# moc2.net
KiCad netlist of a schematic drawn in EAGLE
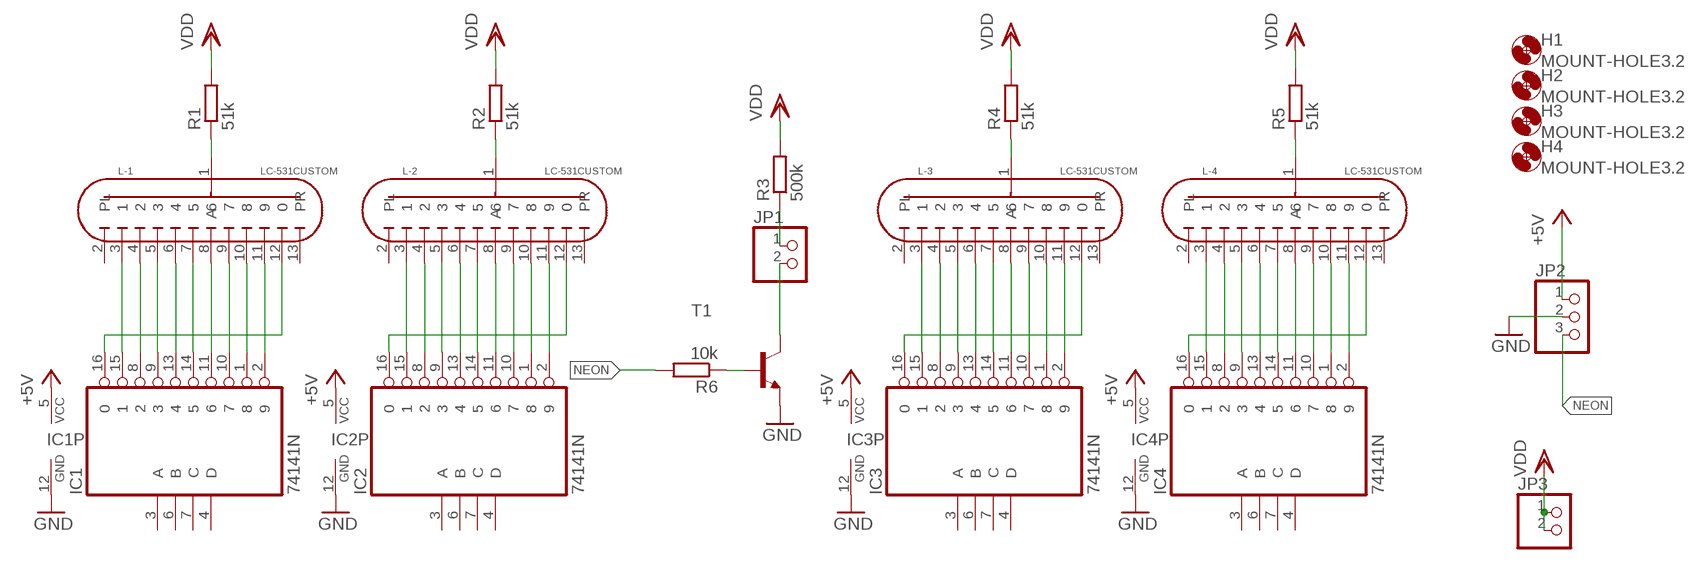
[diagram p0: schematic, sheet 1]

(export (version "E")
  (design (tool "Eeschema 10.0.6"))
  (components
    (comp (ref "H1")
      (value "MOUNT-HOLE3.2")
      (footprint "eagle-import:3,2")
      (libsource (lib "eagle-import") (part "MOUNT-HOLE3.2"))
    )
    (comp (ref "H2")
      (value "MOUNT-HOLE3.2")
      (footprint "eagle-import:3,2")
      (libsource (lib "eagle-import") (part "MOUNT-HOLE3.2"))
    )
    (comp (ref "H3")
      (value "MOUNT-HOLE3.2")
      (footprint "eagle-import:3,2")
      (libsource (lib "eagle-import") (part "MOUNT-HOLE3.2"))
    )
    (comp (ref "H4")
      (value "MOUNT-HOLE3.2")
      (footprint "eagle-import:3,2")
      (libsource (lib "eagle-import") (part "MOUNT-HOLE3.2"))
    )
    (comp (ref "IC1")
      (value "74141N")
      (footprint "eagle-import:DIL16")
      (fields (field (name "SPICEPREFIX") "X"))
      (libsource (lib "eagle-import") (part "74141N"))
    )
    (comp (ref "IC2")
      (value "74141N")
      (footprint "eagle-import:DIL16")
      (libsource (lib "eagle-import") (part "74141N"))
    )
    (comp (ref "IC3")
      (value "74141N")
      (footprint "eagle-import:DIL16")
      (fields (field (name "SPICEPREFIX") "X"))
      (libsource (lib "eagle-import") (part "74141N"))
    )
    (comp (ref "IC4")
      (value "74141N")
      (footprint "eagle-import:DIL16")
      (libsource (lib "eagle-import") (part "74141N"))
    )
    (comp (ref "JP1")
      (value "PINHD-1X2")
      (footprint "eagle-import:1X02")
      (libsource (lib "eagle-import") (part "PINHD-1X2"))
    )
    (comp (ref "JP2")
      (value "PINHD-1X3/90")
      (footprint "eagle-import:1X03_90")
      (libsource (lib "eagle-import") (part "PINHD-1X3/90"))
    )
    (comp (ref "JP3")
      (value "PINHD-1X2/90")
      (footprint "eagle-import:1X02_90")
      (libsource (lib "eagle-import") (part "PINHD-1X2/90"))
    )
    (comp (ref "L-1")
      (value "LC-531CUSTOM")
      (footprint "eagle-import:LC-531_PIN_SOCKET")
      (libsource (lib "eagle-import") (part "LC-531CUSTOM"))
    )
    (comp (ref "L-2")
      (value "LC-531CUSTOM")
      (footprint "eagle-import:LC-531_PIN_SOCKET")
      (libsource (lib "eagle-import") (part "LC-531CUSTOM"))
    )
    (comp (ref "L-3")
      (value "LC-531CUSTOM")
      (footprint "eagle-import:LC-531_PIN_SOCKET")
      (libsource (lib "eagle-import") (part "LC-531CUSTOM"))
    )
    (comp (ref "L-4")
      (value "LC-531CUSTOM")
      (footprint "eagle-import:LC-531_PIN_SOCKET")
      (libsource (lib "eagle-import") (part "LC-531CUSTOM"))
    )
    (comp (ref "R1")
      (value "51k")
      (footprint "eagle-import:0207_10")
      (libsource (lib "eagle-import") (part "R-EU_0207/10"))
    )
    (comp (ref "R2")
      (value "51k")
      (footprint "eagle-import:0207_10")
      (libsource (lib "eagle-import") (part "R-EU_0207/10"))
    )
    (comp (ref "R3")
      (value "500k")
      (footprint "eagle-import:0207_10")
      (libsource (lib "eagle-import") (part "R-EU_0207/10"))
    )
    (comp (ref "R4")
      (value "51k")
      (footprint "eagle-import:0207_10")
      (libsource (lib "eagle-import") (part "R-EU_0207/10"))
    )
    (comp (ref "R5")
      (value "51k")
      (footprint "eagle-import:0207_10")
      (libsource (lib "eagle-import") (part "R-EU_0207/10"))
    )
    (comp (ref "R6")
      (value "10k")
      (footprint "eagle-import:0207_10")
      (libsource (lib "eagle-import") (part "R-EU_0207/10"))
    )
    (comp (ref "T1")
      (value "BF422-NPN-TO92-BCE")
      (footprint "eagle-import:TO92-BCE")
      (libsource (lib "eagle-import") (part "-NPN-TO92-BCEBF422"))
    )
  )
  (nets
    (net (code "1") (name "+5V") (class "Default")
      (node (ref "IC1") (pin "5") (pinfunction "VCC_5") (pintype "power_in"))
      (node (ref "IC2") (pin "5") (pinfunction "VCC_5") (pintype "power_in"))
      (node (ref "IC3") (pin "5") (pinfunction "VCC_5") (pintype "power_in"))
      (node (ref "IC4") (pin "5") (pinfunction "VCC_5") (pintype "power_in"))
      (node (ref "JP2") (pin "1") (pinfunction "1_1") (pintype "passive"))
    )
    (net (code "2") (name "GND") (class "Default")
      (node (ref "IC1") (pin "12") (pinfunction "GND_12") (pintype "power_in"))
      (node (ref "IC2") (pin "12") (pinfunction "GND_12") (pintype "power_in"))
      (node (ref "IC3") (pin "12") (pinfunction "GND_12") (pintype "power_in"))
      (node (ref "IC4") (pin "12") (pinfunction "GND_12") (pintype "power_in"))
      (node (ref "JP2") (pin "2") (pinfunction "2_2") (pintype "passive"))
      (node (ref "T1") (pin "E") (pinfunction "E_E") (pintype "passive"))
    )
    (net (code "3") (name "NEON") (class "Default")
      (node (ref "JP2") (pin "3") (pinfunction "3_3") (pintype "passive"))
      (node (ref "R6") (pin "2") (pinfunction "2_2") (pintype "passive"))
    )
    (net (code "4") (name "Net-(IC1A-0)") (class "Default")
      (node (ref "IC1") (pin "16") (pinfunction "0_16") (pintype "open_collector"))
      (node (ref "L-1") (pin "12") (pinfunction "0_12") (pintype "bidirectional"))
    )
    (net (code "5") (name "Net-(IC1A-1)") (class "Default")
      (node (ref "IC1") (pin "15") (pinfunction "1_15") (pintype "open_collector"))
      (node (ref "L-1") (pin "3") (pinfunction "1_3") (pintype "bidirectional"))
    )
    (net (code "6") (name "Net-(IC1A-2)") (class "Default")
      (node (ref "IC1") (pin "8") (pinfunction "2_8") (pintype "open_collector"))
      (node (ref "L-1") (pin "4") (pinfunction "2_4") (pintype "bidirectional"))
    )
    (net (code "7") (name "Net-(IC1A-3)") (class "Default")
      (node (ref "IC1") (pin "9") (pinfunction "3_9") (pintype "open_collector"))
      (node (ref "L-1") (pin "5") (pinfunction "3_5") (pintype "bidirectional"))
    )
    (net (code "8") (name "Net-(IC1A-4)") (class "Default")
      (node (ref "IC1") (pin "13") (pinfunction "4_13") (pintype "open_collector"))
      (node (ref "L-1") (pin "6") (pinfunction "4_6") (pintype "bidirectional"))
    )
    (net (code "9") (name "Net-(IC1A-5)") (class "Default")
      (node (ref "IC1") (pin "14") (pinfunction "5_14") (pintype "open_collector"))
      (node (ref "L-1") (pin "7") (pinfunction "5_7") (pintype "bidirectional"))
    )
    (net (code "10") (name "Net-(IC1A-6)") (class "Default")
      (node (ref "IC1") (pin "11") (pinfunction "6_11") (pintype "open_collector"))
      (node (ref "L-1") (pin "8") (pinfunction "6_8") (pintype "bidirectional"))
    )
    (net (code "11") (name "Net-(IC1A-7)") (class "Default")
      (node (ref "IC1") (pin "10") (pinfunction "7_10") (pintype "open_collector"))
      (node (ref "L-1") (pin "9") (pinfunction "7_9") (pintype "bidirectional"))
    )
    (net (code "12") (name "Net-(IC1A-8)") (class "Default")
      (node (ref "IC1") (pin "1") (pinfunction "8_1") (pintype "open_collector"))
      (node (ref "L-1") (pin "10") (pinfunction "8_10") (pintype "bidirectional"))
    )
    (net (code "13") (name "Net-(IC1A-9)") (class "Default")
      (node (ref "IC1") (pin "2") (pinfunction "9_2") (pintype "open_collector"))
      (node (ref "L-1") (pin "11") (pinfunction "9_11") (pintype "bidirectional"))
    )
    (net (code "14") (name "Net-(IC2A-0)") (class "Default")
      (node (ref "IC2") (pin "16") (pinfunction "0_16") (pintype "open_collector"))
      (node (ref "L-2") (pin "12") (pinfunction "0_12") (pintype "bidirectional"))
    )
    (net (code "15") (name "Net-(IC2A-1)") (class "Default")
      (node (ref "IC2") (pin "15") (pinfunction "1_15") (pintype "open_collector"))
      (node (ref "L-2") (pin "3") (pinfunction "1_3") (pintype "bidirectional"))
    )
    (net (code "16") (name "Net-(IC2A-2)") (class "Default")
      (node (ref "IC2") (pin "8") (pinfunction "2_8") (pintype "open_collector"))
      (node (ref "L-2") (pin "4") (pinfunction "2_4") (pintype "bidirectional"))
    )
    (net (code "17") (name "Net-(IC2A-3)") (class "Default")
      (node (ref "IC2") (pin "9") (pinfunction "3_9") (pintype "open_collector"))
      (node (ref "L-2") (pin "5") (pinfunction "3_5") (pintype "bidirectional"))
    )
    (net (code "18") (name "Net-(IC2A-4)") (class "Default")
      (node (ref "IC2") (pin "13") (pinfunction "4_13") (pintype "open_collector"))
      (node (ref "L-2") (pin "6") (pinfunction "4_6") (pintype "bidirectional"))
    )
    (net (code "19") (name "Net-(IC2A-5)") (class "Default")
      (node (ref "IC2") (pin "14") (pinfunction "5_14") (pintype "open_collector"))
      (node (ref "L-2") (pin "7") (pinfunction "5_7") (pintype "bidirectional"))
    )
    (net (code "20") (name "Net-(IC2A-6)") (class "Default")
      (node (ref "IC2") (pin "11") (pinfunction "6_11") (pintype "open_collector"))
      (node (ref "L-2") (pin "8") (pinfunction "6_8") (pintype "bidirectional"))
    )
    (net (code "21") (name "Net-(IC2A-7)") (class "Default")
      (node (ref "IC2") (pin "10") (pinfunction "7_10") (pintype "open_collector"))
      (node (ref "L-2") (pin "9") (pinfunction "7_9") (pintype "bidirectional"))
    )
    (net (code "22") (name "Net-(IC2A-8)") (class "Default")
      (node (ref "IC2") (pin "1") (pinfunction "8_1") (pintype "open_collector"))
      (node (ref "L-2") (pin "10") (pinfunction "8_10") (pintype "bidirectional"))
    )
    (net (code "23") (name "Net-(IC2A-9)") (class "Default")
      (node (ref "IC2") (pin "2") (pinfunction "9_2") (pintype "open_collector"))
      (node (ref "L-2") (pin "11") (pinfunction "9_11") (pintype "bidirectional"))
    )
    (net (code "24") (name "Net-(IC3A-0)") (class "Default")
      (node (ref "IC3") (pin "16") (pinfunction "0_16") (pintype "open_collector"))
      (node (ref "L-3") (pin "12") (pinfunction "0_12") (pintype "bidirectional"))
    )
    (net (code "25") (name "Net-(IC3A-1)") (class "Default")
      (node (ref "IC3") (pin "15") (pinfunction "1_15") (pintype "open_collector"))
      (node (ref "L-3") (pin "3") (pinfunction "1_3") (pintype "bidirectional"))
    )
    (net (code "26") (name "Net-(IC3A-2)") (class "Default")
      (node (ref "IC3") (pin "8") (pinfunction "2_8") (pintype "open_collector"))
      (node (ref "L-3") (pin "4") (pinfunction "2_4") (pintype "bidirectional"))
    )
    (net (code "27") (name "Net-(IC3A-3)") (class "Default")
      (node (ref "IC3") (pin "9") (pinfunction "3_9") (pintype "open_collector"))
      (node (ref "L-3") (pin "5") (pinfunction "3_5") (pintype "bidirectional"))
    )
    (net (code "28") (name "Net-(IC3A-4)") (class "Default")
      (node (ref "IC3") (pin "13") (pinfunction "4_13") (pintype "open_collector"))
      (node (ref "L-3") (pin "6") (pinfunction "4_6") (pintype "bidirectional"))
    )
    (net (code "29") (name "Net-(IC3A-5)") (class "Default")
      (node (ref "IC3") (pin "14") (pinfunction "5_14") (pintype "open_collector"))
      (node (ref "L-3") (pin "7") (pinfunction "5_7") (pintype "bidirectional"))
    )
    (net (code "30") (name "Net-(IC3A-6)") (class "Default")
      (node (ref "IC3") (pin "11") (pinfunction "6_11") (pintype "open_collector"))
      (node (ref "L-3") (pin "8") (pinfunction "6_8") (pintype "bidirectional"))
    )
    (net (code "31") (name "Net-(IC3A-7)") (class "Default")
      (node (ref "IC3") (pin "10") (pinfunction "7_10") (pintype "open_collector"))
      (node (ref "L-3") (pin "9") (pinfunction "7_9") (pintype "bidirectional"))
    )
    (net (code "32") (name "Net-(IC3A-8)") (class "Default")
      (node (ref "IC3") (pin "1") (pinfunction "8_1") (pintype "open_collector"))
      (node (ref "L-3") (pin "10") (pinfunction "8_10") (pintype "bidirectional"))
    )
    (net (code "33") (name "Net-(IC3A-9)") (class "Default")
      (node (ref "IC3") (pin "2") (pinfunction "9_2") (pintype "open_collector"))
      (node (ref "L-3") (pin "11") (pinfunction "9_11") (pintype "bidirectional"))
    )
    (net (code "34") (name "Net-(IC4A-0)") (class "Default")
      (node (ref "IC4") (pin "16") (pinfunction "0_16") (pintype "open_collector"))
      (node (ref "L-4") (pin "12") (pinfunction "0_12") (pintype "bidirectional"))
    )
    (net (code "35") (name "Net-(IC4A-1)") (class "Default")
      (node (ref "IC4") (pin "15") (pinfunction "1_15") (pintype "open_collector"))
      (node (ref "L-4") (pin "3") (pinfunction "1_3") (pintype "bidirectional"))
    )
    (net (code "36") (name "Net-(IC4A-2)") (class "Default")
      (node (ref "IC4") (pin "8") (pinfunction "2_8") (pintype "open_collector"))
      (node (ref "L-4") (pin "4") (pinfunction "2_4") (pintype "bidirectional"))
    )
    (net (code "37") (name "Net-(IC4A-3)") (class "Default")
      (node (ref "IC4") (pin "9") (pinfunction "3_9") (pintype "open_collector"))
      (node (ref "L-4") (pin "5") (pinfunction "3_5") (pintype "bidirectional"))
    )
    (net (code "38") (name "Net-(IC4A-4)") (class "Default")
      (node (ref "IC4") (pin "13") (pinfunction "4_13") (pintype "open_collector"))
      (node (ref "L-4") (pin "6") (pinfunction "4_6") (pintype "bidirectional"))
    )
    (net (code "39") (name "Net-(IC4A-5)") (class "Default")
      (node (ref "IC4") (pin "14") (pinfunction "5_14") (pintype "open_collector"))
      (node (ref "L-4") (pin "7") (pinfunction "5_7") (pintype "bidirectional"))
    )
    (net (code "40") (name "Net-(IC4A-6)") (class "Default")
      (node (ref "IC4") (pin "11") (pinfunction "6_11") (pintype "open_collector"))
      (node (ref "L-4") (pin "8") (pinfunction "6_8") (pintype "bidirectional"))
    )
    (net (code "41") (name "Net-(IC4A-7)") (class "Default")
      (node (ref "IC4") (pin "10") (pinfunction "7_10") (pintype "open_collector"))
      (node (ref "L-4") (pin "9") (pinfunction "7_9") (pintype "bidirectional"))
    )
    (net (code "42") (name "Net-(IC4A-8)") (class "Default")
      (node (ref "IC4") (pin "1") (pinfunction "8_1") (pintype "open_collector"))
      (node (ref "L-4") (pin "10") (pinfunction "8_10") (pintype "bidirectional"))
    )
    (net (code "43") (name "Net-(IC4A-9)") (class "Default")
      (node (ref "IC4") (pin "2") (pinfunction "9_2") (pintype "open_collector"))
      (node (ref "L-4") (pin "11") (pinfunction "9_11") (pintype "bidirectional"))
    )
    (net (code "44") (name "Net-(JP1-Pad1)") (class "Default")
      (node (ref "JP1") (pin "1") (pinfunction "1_1") (pintype "passive"))
      (node (ref "R3") (pin "1") (pinfunction "1_1") (pintype "passive"))
    )
    (net (code "45") (name "Net-(JP1-Pad2)") (class "Default")
      (node (ref "JP1") (pin "2") (pinfunction "2_2") (pintype "passive"))
      (node (ref "T1") (pin "C") (pinfunction "C_C") (pintype "passive"))
    )
    (net (code "46") (name "Net-(L-1-A)") (class "Default")
      (node (ref "L-1") (pin "1") (pinfunction "A_1") (pintype "bidirectional"))
      (node (ref "R1") (pin "1") (pinfunction "1_1") (pintype "passive"))
    )
    (net (code "47") (name "Net-(L-2-A)") (class "Default")
      (node (ref "L-2") (pin "1") (pinfunction "A_1") (pintype "bidirectional"))
      (node (ref "R2") (pin "1") (pinfunction "1_1") (pintype "passive"))
    )
    (net (code "48") (name "Net-(L-3-A)") (class "Default")
      (node (ref "L-3") (pin "1") (pinfunction "A_1") (pintype "bidirectional"))
      (node (ref "R4") (pin "1") (pinfunction "1_1") (pintype "passive"))
    )
    (net (code "49") (name "Net-(L-4-A)") (class "Default")
      (node (ref "L-4") (pin "1") (pinfunction "A_1") (pintype "bidirectional"))
      (node (ref "R5") (pin "1") (pinfunction "1_1") (pintype "passive"))
    )
    (net (code "50") (name "Net-(R6-Pad1)") (class "Default")
      (node (ref "R6") (pin "1") (pinfunction "1_1") (pintype "passive"))
      (node (ref "T1") (pin "B") (pinfunction "B_B") (pintype "passive"))
    )
    (net (code "51") (name "VDD") (class "Default")
      (node (ref "JP3") (pin "1") (pinfunction "1_1") (pintype "passive"))
      (node (ref "JP3") (pin "2") (pinfunction "2_2") (pintype "passive"))
      (node (ref "R1") (pin "2") (pinfunction "2_2") (pintype "passive"))
      (node (ref "R2") (pin "2") (pinfunction "2_2") (pintype "passive"))
      (node (ref "R3") (pin "2") (pinfunction "2_2") (pintype "passive"))
      (node (ref "R4") (pin "2") (pinfunction "2_2") (pintype "passive"))
      (node (ref "R5") (pin "2") (pinfunction "2_2") (pintype "passive"))
    )
    (net (code "52") (name "unconnected-(IC1A-A-Pad3)") (class "Default")
      (node (ref "IC1") (pin "3") (pinfunction "A_3") (pintype "input"))
    )
    (net (code "53") (name "unconnected-(IC1A-B-Pad6)") (class "Default")
      (node (ref "IC1") (pin "6") (pinfunction "B_6") (pintype "input"))
    )
    (net (code "54") (name "unconnected-(IC1A-C-Pad7)") (class "Default")
      (node (ref "IC1") (pin "7") (pinfunction "C_7") (pintype "input"))
    )
    (net (code "55") (name "unconnected-(IC1A-D-Pad4)") (class "Default")
      (node (ref "IC1") (pin "4") (pinfunction "D_4") (pintype "input"))
    )
    (net (code "56") (name "unconnected-(IC2A-A-Pad3)") (class "Default")
      (node (ref "IC2") (pin "3") (pinfunction "A_3") (pintype "input"))
    )
    (net (code "57") (name "unconnected-(IC2A-B-Pad6)") (class "Default")
      (node (ref "IC2") (pin "6") (pinfunction "B_6") (pintype "input"))
    )
    (net (code "58") (name "unconnected-(IC2A-C-Pad7)") (class "Default")
      (node (ref "IC2") (pin "7") (pinfunction "C_7") (pintype "input"))
    )
    (net (code "59") (name "unconnected-(IC2A-D-Pad4)") (class "Default")
      (node (ref "IC2") (pin "4") (pinfunction "D_4") (pintype "input"))
    )
    (net (code "60") (name "unconnected-(IC3A-A-Pad3)") (class "Default")
      (node (ref "IC3") (pin "3") (pinfunction "A_3") (pintype "input"))
    )
    (net (code "61") (name "unconnected-(IC3A-B-Pad6)") (class "Default")
      (node (ref "IC3") (pin "6") (pinfunction "B_6") (pintype "input"))
    )
    (net (code "62") (name "unconnected-(IC3A-C-Pad7)") (class "Default")
      (node (ref "IC3") (pin "7") (pinfunction "C_7") (pintype "input"))
    )
    (net (code "63") (name "unconnected-(IC3A-D-Pad4)") (class "Default")
      (node (ref "IC3") (pin "4") (pinfunction "D_4") (pintype "input"))
    )
    (net (code "64") (name "unconnected-(IC4A-A-Pad3)") (class "Default")
      (node (ref "IC4") (pin "3") (pinfunction "A_3") (pintype "input"))
    )
    (net (code "65") (name "unconnected-(IC4A-B-Pad6)") (class "Default")
      (node (ref "IC4") (pin "6") (pinfunction "B_6") (pintype "input"))
    )
    (net (code "66") (name "unconnected-(IC4A-C-Pad7)") (class "Default")
      (node (ref "IC4") (pin "7") (pinfunction "C_7") (pintype "input"))
    )
    (net (code "67") (name "unconnected-(IC4A-D-Pad4)") (class "Default")
      (node (ref "IC4") (pin "4") (pinfunction "D_4") (pintype "input"))
    )
    (net (code "68") (name "unconnected-(L-1-PL-Pad2)") (class "Default")
      (node (ref "L-1") (pin "2") (pinfunction "PL_2") (pintype "bidirectional"))
    )
    (net (code "69") (name "unconnected-(L-1-PR-Pad13)") (class "Default")
      (node (ref "L-1") (pin "13") (pinfunction "PR_13") (pintype "bidirectional"))
    )
    (net (code "70") (name "unconnected-(L-2-PL-Pad2)") (class "Default")
      (node (ref "L-2") (pin "2") (pinfunction "PL_2") (pintype "bidirectional"))
    )
    (net (code "71") (name "unconnected-(L-2-PR-Pad13)") (class "Default")
      (node (ref "L-2") (pin "13") (pinfunction "PR_13") (pintype "bidirectional"))
    )
    (net (code "72") (name "unconnected-(L-3-PL-Pad2)") (class "Default")
      (node (ref "L-3") (pin "2") (pinfunction "PL_2") (pintype "bidirectional"))
    )
    (net (code "73") (name "unconnected-(L-3-PR-Pad13)") (class "Default")
      (node (ref "L-3") (pin "13") (pinfunction "PR_13") (pintype "bidirectional"))
    )
    (net (code "74") (name "unconnected-(L-4-PL-Pad2)") (class "Default")
      (node (ref "L-4") (pin "2") (pinfunction "PL_2") (pintype "bidirectional"))
    )
    (net (code "75") (name "unconnected-(L-4-PR-Pad13)") (class "Default")
      (node (ref "L-4") (pin "13") (pinfunction "PR_13") (pintype "bidirectional"))
    )
  )
)
